# SparkFun_tDof-TMF8820_HQ.net
KiCad netlist of a schematic drawn in EAGLE
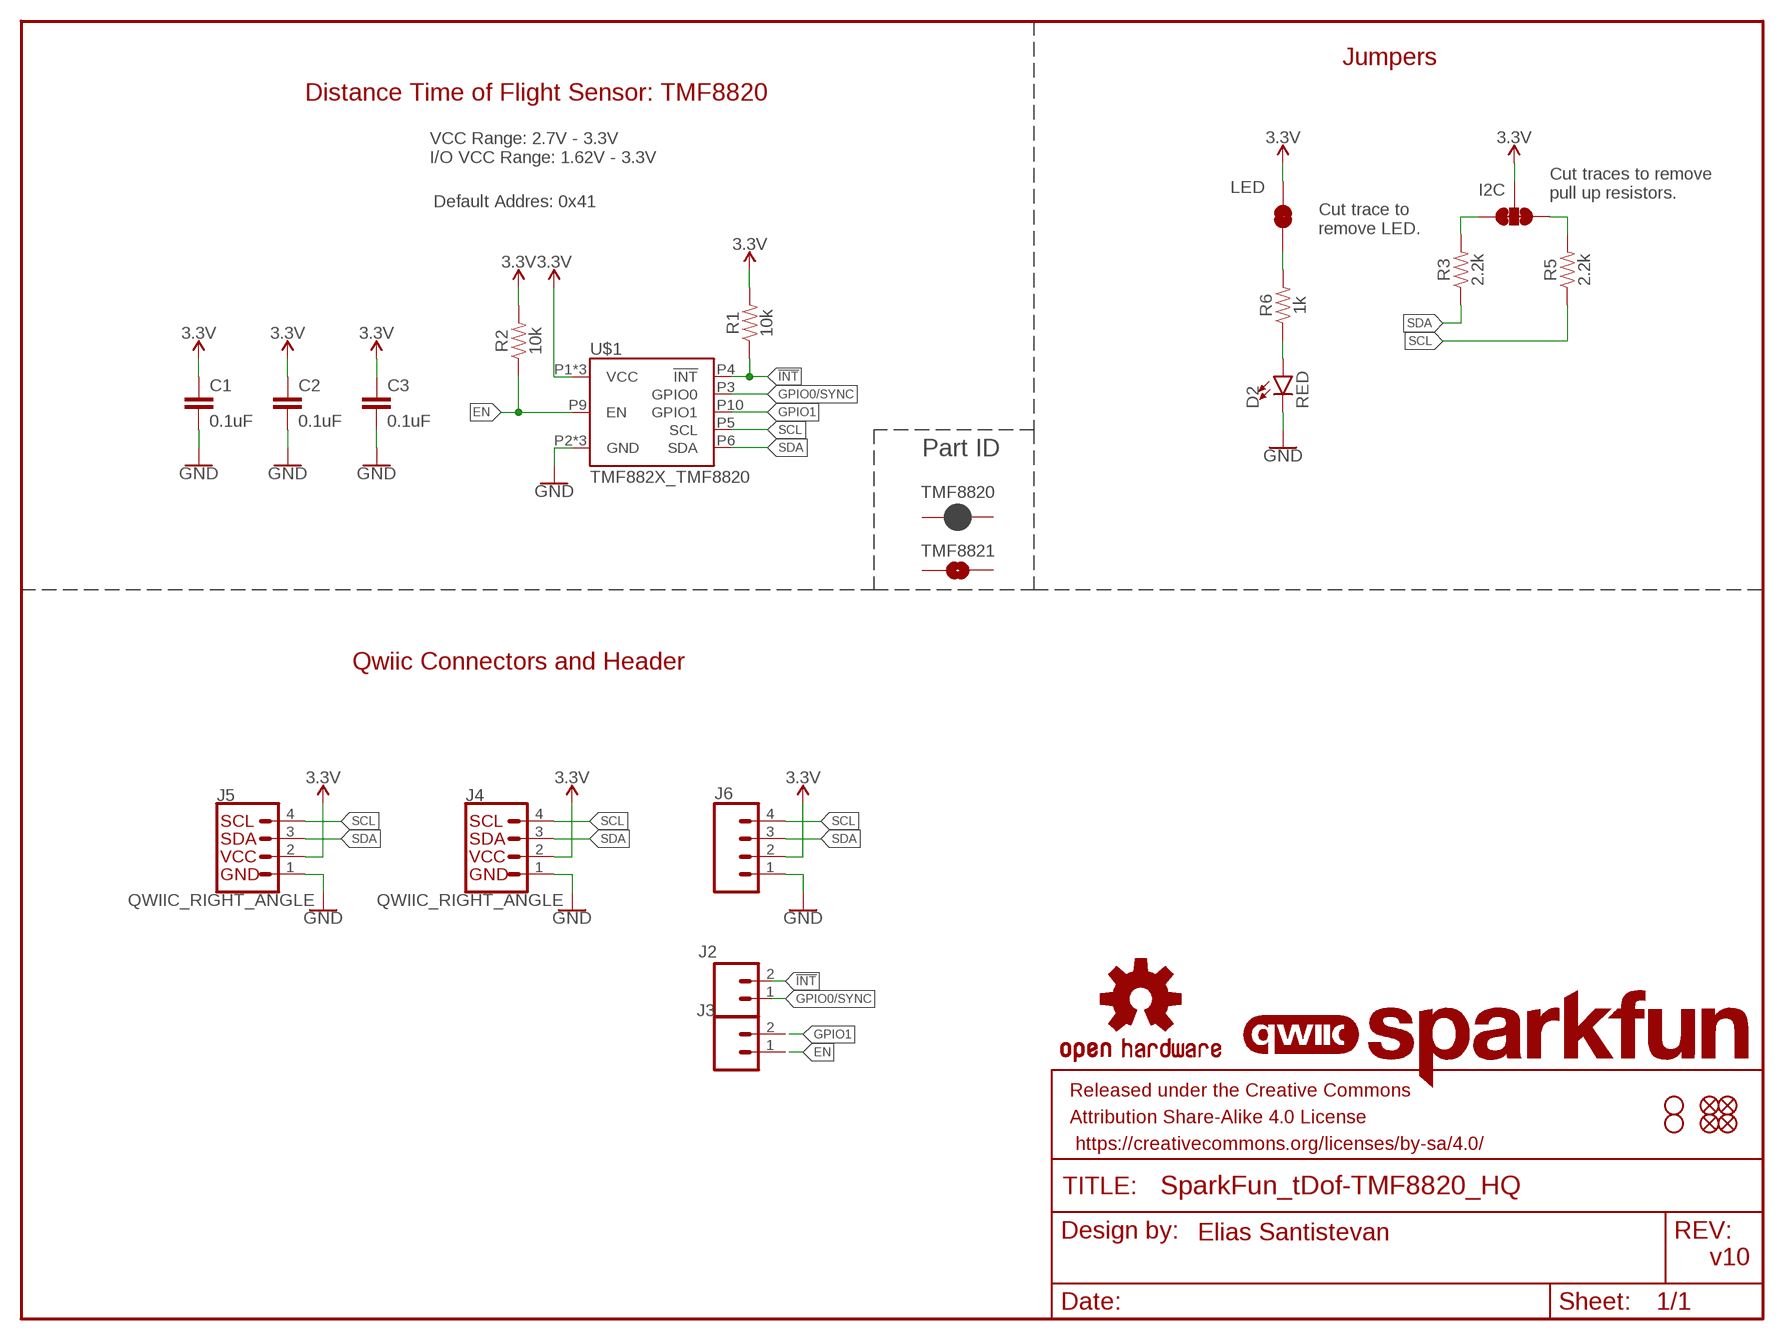
[diagram p0: schematic, sheet 1]

(export (version "E")
  (design (tool "Eeschema 10.0.6"))
  (components
    (comp (ref "C1")
      (value "0.1uF")
      (footprint "eagle-import:0402-TIGHT")
      (libsource (lib "eagle-import") (part "0.1UF-0402T-6.3V-10%-X7R"))
    )
    (comp (ref "C2")
      (value "0.1uF")
      (footprint "eagle-import:0402-TIGHT")
      (libsource (lib "eagle-import") (part "0.1UF-0402T-6.3V-10%-X7R"))
    )
    (comp (ref "C3")
      (value "0.1uF")
      (footprint "eagle-import:0402-TIGHT")
      (libsource (lib "eagle-import") (part "0.1UF-0402T-6.3V-10%-X7R"))
    )
    (comp (ref "D2")
      (value "RED")
      (footprint "eagle-import:LED-0603")
      (libsource (lib "eagle-import") (part "LED-RED0603"))
    )
    (comp (ref "FD5")
      (value "FIDUCIALUFIDUCIAL")
      (footprint "eagle-import:FIDUCIAL-MICRO")
      (libsource (lib "eagle-import") (part "FIDUCIALUFIDUCIAL"))
    )
    (comp (ref "FD6")
      (value "FIDUCIALUFIDUCIAL")
      (footprint "eagle-import:FIDUCIAL-MICRO")
      (libsource (lib "eagle-import") (part "FIDUCIALUFIDUCIAL"))
    )
    (comp (ref "FD7")
      (value "FIDUCIALUFIDUCIAL")
      (footprint "eagle-import:FIDUCIAL-MICRO")
      (libsource (lib "eagle-import") (part "FIDUCIALUFIDUCIAL"))
    )
    (comp (ref "FD8")
      (value "FIDUCIALUFIDUCIAL")
      (footprint "eagle-import:FIDUCIAL-MICRO")
      (libsource (lib "eagle-import") (part "FIDUCIALUFIDUCIAL"))
    )
    (comp (ref "FRAME2")
      (value "FRAME-LETTER")
      (footprint "eagle-import:CREATIVE_COMMONS")
      (libsource (lib "eagle-import") (part "FRAME-LETTER"))
    )
    (comp (ref "H7")
      (value "STAND-OFFTIGHT")
      (footprint "eagle-import:STAND-OFF-TIGHT")
      (libsource (lib "eagle-import") (part "STAND-OFFTIGHT"))
    )
    (comp (ref "H8")
      (value "STAND-OFFTIGHT")
      (footprint "eagle-import:STAND-OFF-TIGHT")
      (libsource (lib "eagle-import") (part "STAND-OFFTIGHT"))
    )
    (comp (ref "I2C")
      (value "I2C_PU")
      (footprint "eagle-import:SMT-JUMPER_3_2-NC_TRACE_SILK")
      (libsource (lib "eagle-import") (part "JUMPER-SMT_3_2-NC_TRACE_SILK"))
    )
    (comp (ref "J2")
      (value "CONN_021X02_NO_SILK")
      (footprint "eagle-import:1X02_NO_SILK")
      (libsource (lib "eagle-import") (part "CONN_021X02_NO_SILK"))
    )
    (comp (ref "J3")
      (value "CONN_021X02_NO_SILK")
      (footprint "eagle-import:1X02_NO_SILK")
      (libsource (lib "eagle-import") (part "CONN_021X02_NO_SILK"))
    )
    (comp (ref "J4")
      (value "QWIIC_RIGHT_ANGLE")
      (footprint "eagle-import:JST04_1MM_RA")
      (libsource (lib "eagle-import") (part "QWIIC_CONNECTORJS-1MM"))
    )
    (comp (ref "J5")
      (value "QWIIC_RIGHT_ANGLE")
      (footprint "eagle-import:JST04_1MM_RA")
      (libsource (lib "eagle-import") (part "QWIIC_CONNECTORJS-1MM"))
    )
    (comp (ref "J6")
      (value "CONN_041X04_NO_SILK")
      (footprint "eagle-import:1X04_NO_SILK")
      (libsource (lib "eagle-import") (part "CONN_041X04_NO_SILK"))
    )
    (comp (ref "LED")
      (value "LED")
      (footprint "eagle-import:SMT-JUMPER_2_NC_TRACE_SILK")
      (libsource (lib "eagle-import") (part "JUMPER-SMT_2_NC_TRACE_SILK"))
    )
    (comp (ref "LOGO1")
      (value "SFE_LOGO_NAMEBLANK")
      (footprint "eagle-import:BLANK")
      (libsource (lib "eagle-import") (part "SFE_LOGO_NAMEBLANK"))
    )
    (comp (ref "LOGO2")
      (value "QWIIC_LOGO_3MM")
      (footprint "eagle-import:QWIIC_3MM")
      (libsource (lib "eagle-import") (part "QWIIC_LOGO_3MM"))
    )
    (comp (ref "LOGO3")
      (value "OSHW-LOGONO_SILK")
      (footprint "eagle-import:DUMMY")
      (libsource (lib "eagle-import") (part "OSHW-LOGONO_SILK"))
    )
    (comp (ref "R1")
      (value "10k")
      (footprint "eagle-import:0402-TIGHT")
      (libsource (lib "eagle-import") (part "10KOHM-0402T-1/16W-1%"))
    )
    (comp (ref "R2")
      (value "10k")
      (footprint "eagle-import:0402-TIGHT")
      (libsource (lib "eagle-import") (part "10KOHM-0402T-1/16W-1%"))
    )
    (comp (ref "R3")
      (value "2.2k")
      (footprint "eagle-import:0402-TIGHT")
      (libsource (lib "eagle-import") (part "2.2KOHM-0402T-1/16W-1%"))
    )
    (comp (ref "R5")
      (value "2.2k")
      (footprint "eagle-import:0402-TIGHT")
      (libsource (lib "eagle-import") (part "2.2KOHM-0402T-1/16W-1%"))
    )
    (comp (ref "R6")
      (value "1k")
      (footprint "eagle-import:0402-TIGHT")
      (libsource (lib "eagle-import") (part "1KOHM-0402T-1/16W-1%"))
    )
    (comp (ref "TMF8820")
      (value "JUMPER-SMT_2_NC_PASTE_SILK")
      (footprint "eagle-import:SMT-JUMPER_2_NC_PASTE_SILK")
      (libsource (lib "eagle-import") (part "JUMPER-SMT_2_NC_PASTE_SILK"))
    )
    (comp (ref "TMF8821")
      (value "JUMPER-SMT_2_NO_SILK")
      (footprint "eagle-import:SMT-JUMPER_2_NO_SILK")
      (libsource (lib "eagle-import") (part "JUMPER-SMT_2_NO_SILK"))
    )
    (comp (ref "U$1")
      (value "TMF882X_TMF8820")
      (footprint "eagle-import:TMF882X")
      (libsource (lib "eagle-import") (part "TMF882X_TMF8820"))
    )
  )
  (nets
    (net (code "1") (name "/~{INT}") (class "Default")
      (node (ref "J2") (pin "2") (pinfunction "2_2") (pintype "passive"))
      (node (ref "R1") (pin "1") (pinfunction "1_1") (pintype "passive"))
      (node (ref "U$1") (pin "P4") (pinfunction "~{INT}_P4") (pintype "bidirectional"))
    )
    (net (code "2") (name "3.3V") (class "Default")
      (node (ref "C1") (pin "1") (pinfunction "1_1") (pintype "passive"))
      (node (ref "C2") (pin "1") (pinfunction "1_1") (pintype "passive"))
      (node (ref "C3") (pin "1") (pinfunction "1_1") (pintype "passive"))
      (node (ref "I2C") (pin "2") (pinfunction "2_2") (pintype "passive"))
      (node (ref "J4") (pin "2") (pinfunction "2_2") (pintype "power_in"))
      (node (ref "J5") (pin "2") (pinfunction "2_2") (pintype "power_in"))
      (node (ref "J6") (pin "2") (pinfunction "2_2") (pintype "passive"))
      (node (ref "LED") (pin "2") (pinfunction "2_2") (pintype "passive"))
      (node (ref "R1") (pin "2") (pinfunction "2_2") (pintype "passive"))
      (node (ref "R2") (pin "2") (pinfunction "2_2") (pintype "passive"))
      (node (ref "U$1") (pin "P1") (pinfunction "VCC_P1") (pintype "power_in"))
      (node (ref "U$1") (pin "P12") (pinfunction "VCC_P12") (pintype "power_in"))
      (node (ref "U$1") (pin "P7") (pinfunction "VCC_P7") (pintype "power_in"))
    )
    (net (code "3") (name "EN") (class "Default")
      (node (ref "J3") (pin "1") (pinfunction "1_1") (pintype "passive"))
      (node (ref "R2") (pin "1") (pinfunction "1_1") (pintype "passive"))
      (node (ref "U$1") (pin "P9") (pinfunction "EN_P9") (pintype "input"))
    )
    (net (code "4") (name "GND") (class "Default")
      (node (ref "C1") (pin "2") (pinfunction "2_2") (pintype "passive"))
      (node (ref "C2") (pin "2") (pinfunction "2_2") (pintype "passive"))
      (node (ref "C3") (pin "2") (pinfunction "2_2") (pintype "passive"))
      (node (ref "D2") (pin "C") (pinfunction "C_C") (pintype "passive"))
      (node (ref "J4") (pin "1") (pinfunction "1_1") (pintype "power_in"))
      (node (ref "J5") (pin "1") (pinfunction "1_1") (pintype "power_in"))
      (node (ref "J6") (pin "1") (pinfunction "1_1") (pintype "passive"))
      (node (ref "U$1") (pin "P11") (pinfunction "GND_P11") (pintype "power_in"))
      (node (ref "U$1") (pin "P2") (pinfunction "GND_P2") (pintype "power_in"))
      (node (ref "U$1") (pin "P8") (pinfunction "GND_P8") (pintype "power_in"))
    )
    (net (code "5") (name "GPIO0{slash}SYNC") (class "Default")
      (node (ref "J2") (pin "1") (pinfunction "1_1") (pintype "passive"))
      (node (ref "U$1") (pin "P3") (pinfunction "GPIO0_P3") (pintype "bidirectional"))
    )
    (net (code "6") (name "GPIO1") (class "Default")
      (node (ref "J3") (pin "2") (pinfunction "2_2") (pintype "passive"))
      (node (ref "U$1") (pin "P10") (pinfunction "GPIO1_P10") (pintype "bidirectional"))
    )
    (net (code "7") (name "Net-(D2-PadA)") (class "Default")
      (node (ref "D2") (pin "A") (pinfunction "A_A") (pintype "passive"))
      (node (ref "R6") (pin "1") (pinfunction "1_1") (pintype "passive"))
    )
    (net (code "8") (name "Net-(I2C-Pad1)") (class "Default")
      (node (ref "I2C") (pin "1") (pinfunction "1_1") (pintype "passive"))
      (node (ref "R5") (pin "2") (pinfunction "2_2") (pintype "passive"))
    )
    (net (code "9") (name "Net-(I2C-Pad3)") (class "Default")
      (node (ref "I2C") (pin "3") (pinfunction "3_3") (pintype "passive"))
      (node (ref "R3") (pin "2") (pinfunction "2_2") (pintype "passive"))
    )
    (net (code "10") (name "Net-(LED-Pad1)") (class "Default")
      (node (ref "LED") (pin "1") (pinfunction "1_1") (pintype "passive"))
      (node (ref "R6") (pin "2") (pinfunction "2_2") (pintype "passive"))
    )
    (net (code "11") (name "SCL") (class "Default")
      (node (ref "J4") (pin "4") (pinfunction "4_4") (pintype "passive"))
      (node (ref "J5") (pin "4") (pinfunction "4_4") (pintype "passive"))
      (node (ref "J6") (pin "4") (pinfunction "4_4") (pintype "passive"))
      (node (ref "R5") (pin "1") (pinfunction "1_1") (pintype "passive"))
      (node (ref "U$1") (pin "P5") (pinfunction "SCL_P5") (pintype "bidirectional"))
    )
    (net (code "12") (name "SDA") (class "Default")
      (node (ref "J4") (pin "3") (pinfunction "3_3") (pintype "passive"))
      (node (ref "J5") (pin "3") (pinfunction "3_3") (pintype "passive"))
      (node (ref "J6") (pin "3") (pinfunction "3_3") (pintype "passive"))
      (node (ref "R3") (pin "1") (pinfunction "1_1") (pintype "passive"))
      (node (ref "U$1") (pin "P6") (pinfunction "SDA_P6") (pintype "bidirectional"))
    )
    (net (code "13") (name "unconnected-(TMF8820-Pad1)") (class "Default")
      (node (ref "TMF8820") (pin "1") (pinfunction "1_1") (pintype "passive"))
    )
    (net (code "14") (name "unconnected-(TMF8820-Pad2)") (class "Default")
      (node (ref "TMF8820") (pin "2") (pinfunction "2_2") (pintype "passive"))
    )
    (net (code "15") (name "unconnected-(TMF8821-Pad1)") (class "Default")
      (node (ref "TMF8821") (pin "1") (pinfunction "1_1") (pintype "passive"))
    )
    (net (code "16") (name "unconnected-(TMF8821-Pad2)") (class "Default")
      (node (ref "TMF8821") (pin "2") (pinfunction "2_2") (pintype "passive"))
    )
  )
)
